# Puzzle_Interface.net
KiCad netlist of a schematic drawn in EAGLE
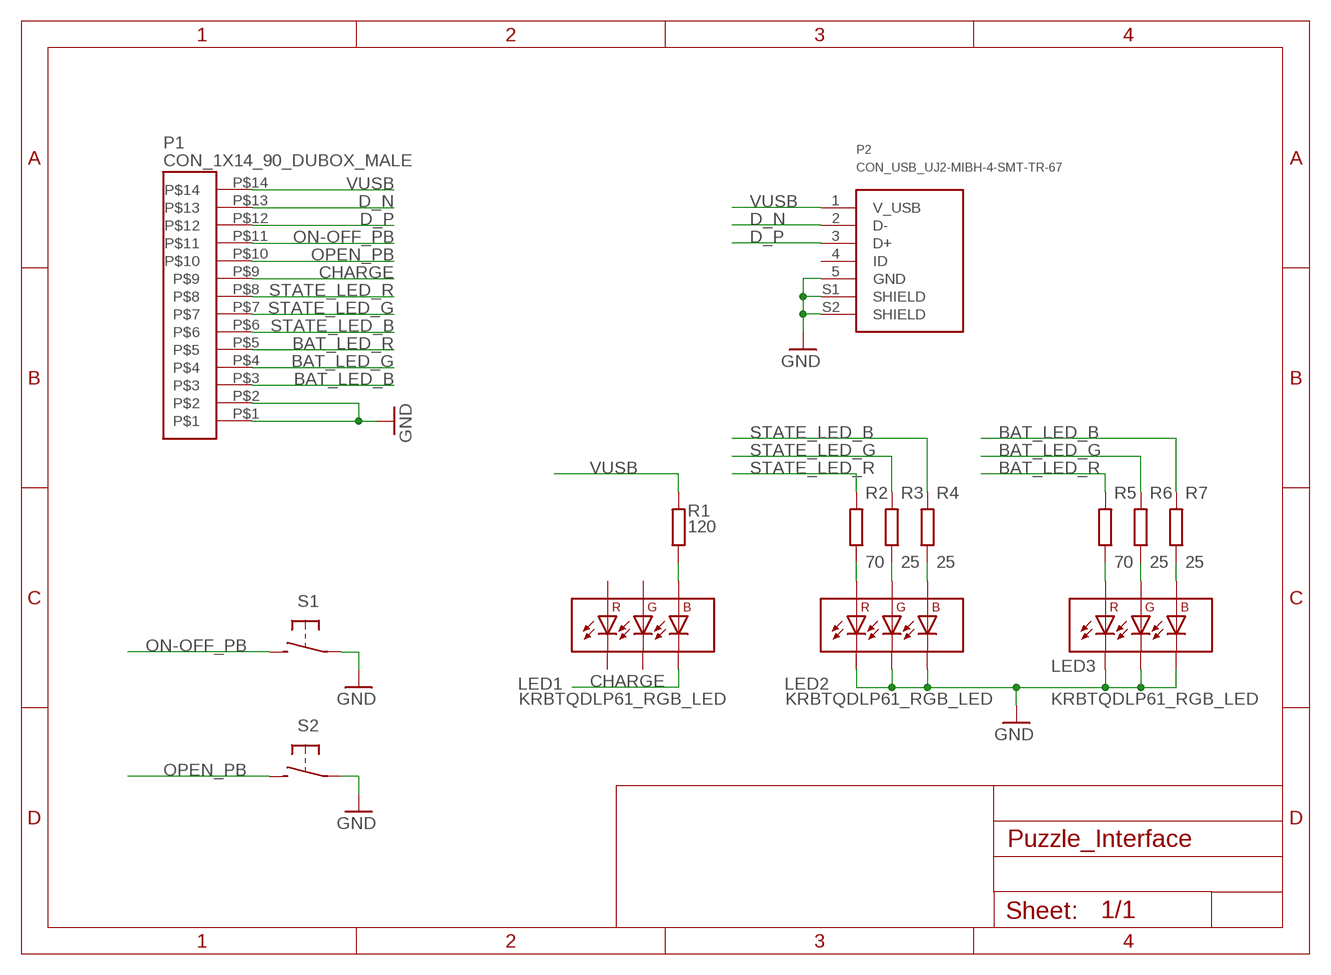
[diagram p0: schematic, sheet 1]

(export (version "E")
  (design (tool "Eeschema 10.0.6"))
  (components
    (comp (ref "LED1")
      (value "KRBTQDLP61_RGB_LED")
      (footprint "eagle-import:KRBTQDLP61_RGB_LED")
      (libsource (lib "eagle-import") (part "KRBTQDLP61_RGB_LED"))
    )
    (comp (ref "LED2")
      (value "KRBTQDLP61_RGB_LED")
      (footprint "eagle-import:KRBTQDLP61_RGB_LED")
      (libsource (lib "eagle-import") (part "KRBTQDLP61_RGB_LED"))
    )
    (comp (ref "LED3")
      (value "KRBTQDLP61_RGB_LED")
      (footprint "eagle-import:KRBTQDLP61_RGB_LED")
      (libsource (lib "eagle-import") (part "KRBTQDLP61_RGB_LED"))
    )
    (comp (ref "P1")
      (value "CON_1X14_90_DUBOX_MALE")
      (footprint "eagle-import:CON_1X14_90_DUBOX_MALE")
      (libsource (lib "eagle-import") (part "CON_1X14_90_DUBOX_MALE"))
    )
    (comp (ref "P2")
      (value "CON_USB_UJ2-MIBH-4-SMT-TR-67")
      (footprint "eagle-import:CON_USB_UJ2-MIBH-4-SMT-TR-67")
      (libsource (lib "eagle-import") (part "CON_USB_UJ2-MIBH-4-SMT-TR-67"))
    )
    (comp (ref "R1")
      (value "120")
      (footprint "eagle-import:0603")
      (libsource (lib "eagle-import") (part "RES_0603"))
    )
    (comp (ref "R2")
      (value "70")
      (footprint "eagle-import:0603")
      (libsource (lib "eagle-import") (part "RES_0603"))
    )
    (comp (ref "R3")
      (value "25")
      (footprint "eagle-import:0603")
      (libsource (lib "eagle-import") (part "RES_0603"))
    )
    (comp (ref "R4")
      (value "25")
      (footprint "eagle-import:0603")
      (libsource (lib "eagle-import") (part "RES_0603"))
    )
    (comp (ref "R5")
      (value "70")
      (footprint "eagle-import:0603")
      (libsource (lib "eagle-import") (part "RES_0603"))
    )
    (comp (ref "R6")
      (value "25")
      (footprint "eagle-import:0603")
      (libsource (lib "eagle-import") (part "RES_0603"))
    )
    (comp (ref "R7")
      (value "25")
      (footprint "eagle-import:0603")
      (libsource (lib "eagle-import") (part "RES_0603"))
    )
    (comp (ref "S1")
      (value "EG5358CT-ND_PB")
      (footprint "eagle-import:EG5358CT-ND_PB")
      (libsource (lib "eagle-import") (part "EG5358CT-ND_PB"))
    )
    (comp (ref "S2")
      (value "EG5358CT-ND_PB")
      (footprint "eagle-import:EG5358CT-ND_PB")
      (libsource (lib "eagle-import") (part "EG5358CT-ND_PB"))
    )
  )
  (nets
    (net (code "1") (name "/BAT_LED_B") (class "Default")
      (node (ref "P1") (pin "P$3") (pinfunction "P$3_P$3") (pintype "bidirectional"))
      (node (ref "R7") (pin "2") (pinfunction "2_2") (pintype "passive"))
    )
    (net (code "2") (name "/BAT_LED_G") (class "Default")
      (node (ref "P1") (pin "P$4") (pinfunction "P$4_P$4") (pintype "bidirectional"))
      (node (ref "R6") (pin "2") (pinfunction "2_2") (pintype "passive"))
    )
    (net (code "3") (name "/BAT_LED_R") (class "Default")
      (node (ref "P1") (pin "P$5") (pinfunction "P$5_P$5") (pintype "bidirectional"))
      (node (ref "R5") (pin "2") (pinfunction "2_2") (pintype "passive"))
    )
    (net (code "4") (name "/CHARGE") (class "Default")
      (node (ref "LED1") (pin "P$4") (pinfunction "BC_P$4") (pintype "passive"))
      (node (ref "P1") (pin "P$9") (pinfunction "P$9_P$9") (pintype "bidirectional"))
    )
    (net (code "5") (name "/D_N") (class "Default")
      (node (ref "P1") (pin "P$13") (pinfunction "P$13_P$13") (pintype "bidirectional"))
      (node (ref "P2") (pin "2") (pinfunction "D-_2") (pintype "bidirectional"))
    )
    (net (code "6") (name "/D_P") (class "Default")
      (node (ref "P1") (pin "P$12") (pinfunction "P$12_P$12") (pintype "bidirectional"))
      (node (ref "P2") (pin "3") (pinfunction "D+_3") (pintype "bidirectional"))
    )
    (net (code "7") (name "/ON-OFF_PB") (class "Default")
      (node (ref "P1") (pin "P$11") (pinfunction "P$11_P$11") (pintype "bidirectional"))
      (node (ref "S1") (pin "2") (pinfunction "S_2") (pintype "passive"))
    )
    (net (code "8") (name "/OPEN_PB") (class "Default")
      (node (ref "P1") (pin "P$10") (pinfunction "P$10_P$10") (pintype "bidirectional"))
      (node (ref "S2") (pin "2") (pinfunction "S_2") (pintype "passive"))
    )
    (net (code "9") (name "/STATE_LED_B") (class "Default")
      (node (ref "P1") (pin "P$6") (pinfunction "P$6_P$6") (pintype "bidirectional"))
      (node (ref "R4") (pin "2") (pinfunction "2_2") (pintype "passive"))
    )
    (net (code "10") (name "/STATE_LED_G") (class "Default")
      (node (ref "P1") (pin "P$7") (pinfunction "P$7_P$7") (pintype "bidirectional"))
      (node (ref "R3") (pin "2") (pinfunction "2_2") (pintype "passive"))
    )
    (net (code "11") (name "/STATE_LED_R") (class "Default")
      (node (ref "P1") (pin "P$8") (pinfunction "P$8_P$8") (pintype "bidirectional"))
      (node (ref "R2") (pin "2") (pinfunction "2_2") (pintype "passive"))
    )
    (net (code "12") (name "/VUSB") (class "Default")
      (node (ref "P1") (pin "P$14") (pinfunction "P$14_P$14") (pintype "bidirectional"))
      (node (ref "P2") (pin "1") (pinfunction "V_USB_1") (pintype "bidirectional"))
      (node (ref "R1") (pin "2") (pinfunction "2_2") (pintype "passive"))
    )
    (net (code "13") (name "GND") (class "Default")
      (node (ref "LED2") (pin "P$3") (pinfunction "GC_P$3") (pintype "passive"))
      (node (ref "LED2") (pin "P$4") (pinfunction "BC_P$4") (pintype "passive"))
      (node (ref "LED2") (pin "P$6") (pinfunction "RC_P$6") (pintype "passive"))
      (node (ref "LED3") (pin "P$3") (pinfunction "GC_P$3") (pintype "passive"))
      (node (ref "LED3") (pin "P$4") (pinfunction "BC_P$4") (pintype "passive"))
      (node (ref "LED3") (pin "P$6") (pinfunction "RC_P$6") (pintype "passive"))
      (node (ref "P1") (pin "P$1") (pinfunction "P$1_P$1") (pintype "bidirectional"))
      (node (ref "P1") (pin "P$2") (pinfunction "P$2_P$2") (pintype "bidirectional"))
      (node (ref "P2") (pin "5") (pinfunction "GND_5") (pintype "bidirectional"))
      (node (ref "P2") (pin "S1") (pinfunction "SHIELD_S1") (pintype "bidirectional"))
      (node (ref "P2") (pin "S2") (pinfunction "SHIELD_S2") (pintype "bidirectional"))
      (node (ref "S1") (pin "1") (pinfunction "P_1") (pintype "passive"))
      (node (ref "S1") (pin "S1") (pinfunction "P_S1") (pintype "passive"))
      (node (ref "S1") (pin "S2") (pinfunction "P_S2") (pintype "passive"))
      (node (ref "S2") (pin "1") (pinfunction "P_1") (pintype "passive"))
      (node (ref "S2") (pin "S1") (pinfunction "P_S1") (pintype "passive"))
      (node (ref "S2") (pin "S2") (pinfunction "P_S2") (pintype "passive"))
    )
    (net (code "14") (name "Net-(LED1-BA)") (class "Default")
      (node (ref "LED1") (pin "P$2") (pinfunction "BA_P$2") (pintype "passive"))
      (node (ref "R1") (pin "1") (pinfunction "1_1") (pintype "passive"))
    )
    (net (code "15") (name "Net-(LED2-BA)") (class "Default")
      (node (ref "LED2") (pin "P$2") (pinfunction "BA_P$2") (pintype "passive"))
      (node (ref "R4") (pin "1") (pinfunction "1_1") (pintype "passive"))
    )
    (net (code "16") (name "Net-(LED2-GA)") (class "Default")
      (node (ref "LED2") (pin "P$1") (pinfunction "GA_P$1") (pintype "passive"))
      (node (ref "R3") (pin "1") (pinfunction "1_1") (pintype "passive"))
    )
    (net (code "17") (name "Net-(LED2-RA)") (class "Default")
      (node (ref "LED2") (pin "P$5") (pinfunction "RA_P$5") (pintype "passive"))
      (node (ref "R2") (pin "1") (pinfunction "1_1") (pintype "passive"))
    )
    (net (code "18") (name "Net-(LED3-BA)") (class "Default")
      (node (ref "LED3") (pin "P$2") (pinfunction "BA_P$2") (pintype "passive"))
      (node (ref "R7") (pin "1") (pinfunction "1_1") (pintype "passive"))
    )
    (net (code "19") (name "Net-(LED3-GA)") (class "Default")
      (node (ref "LED3") (pin "P$1") (pinfunction "GA_P$1") (pintype "passive"))
      (node (ref "R6") (pin "1") (pinfunction "1_1") (pintype "passive"))
    )
    (net (code "20") (name "Net-(LED3-RA)") (class "Default")
      (node (ref "LED3") (pin "P$5") (pinfunction "RA_P$5") (pintype "passive"))
      (node (ref "R5") (pin "1") (pinfunction "1_1") (pintype "passive"))
    )
    (net (code "21") (name "unconnected-(LED1-GA-PadP$1)") (class "Default")
      (node (ref "LED1") (pin "P$1") (pinfunction "GA_P$1") (pintype "passive"))
    )
    (net (code "22") (name "unconnected-(LED1-GC-PadP$3)") (class "Default")
      (node (ref "LED1") (pin "P$3") (pinfunction "GC_P$3") (pintype "passive"))
    )
    (net (code "23") (name "unconnected-(LED1-RA-PadP$5)") (class "Default")
      (node (ref "LED1") (pin "P$5") (pinfunction "RA_P$5") (pintype "passive"))
    )
    (net (code "24") (name "unconnected-(LED1-RC-PadP$6)") (class "Default")
      (node (ref "LED1") (pin "P$6") (pinfunction "RC_P$6") (pintype "passive"))
    )
    (net (code "25") (name "unconnected-(P2-ID-Pad4)") (class "Default")
      (node (ref "P2") (pin "4") (pinfunction "ID_4") (pintype "bidirectional"))
    )
  )
)
